# ardTriggerShield.net
KiCad netlist of a schematic drawn in EAGLE
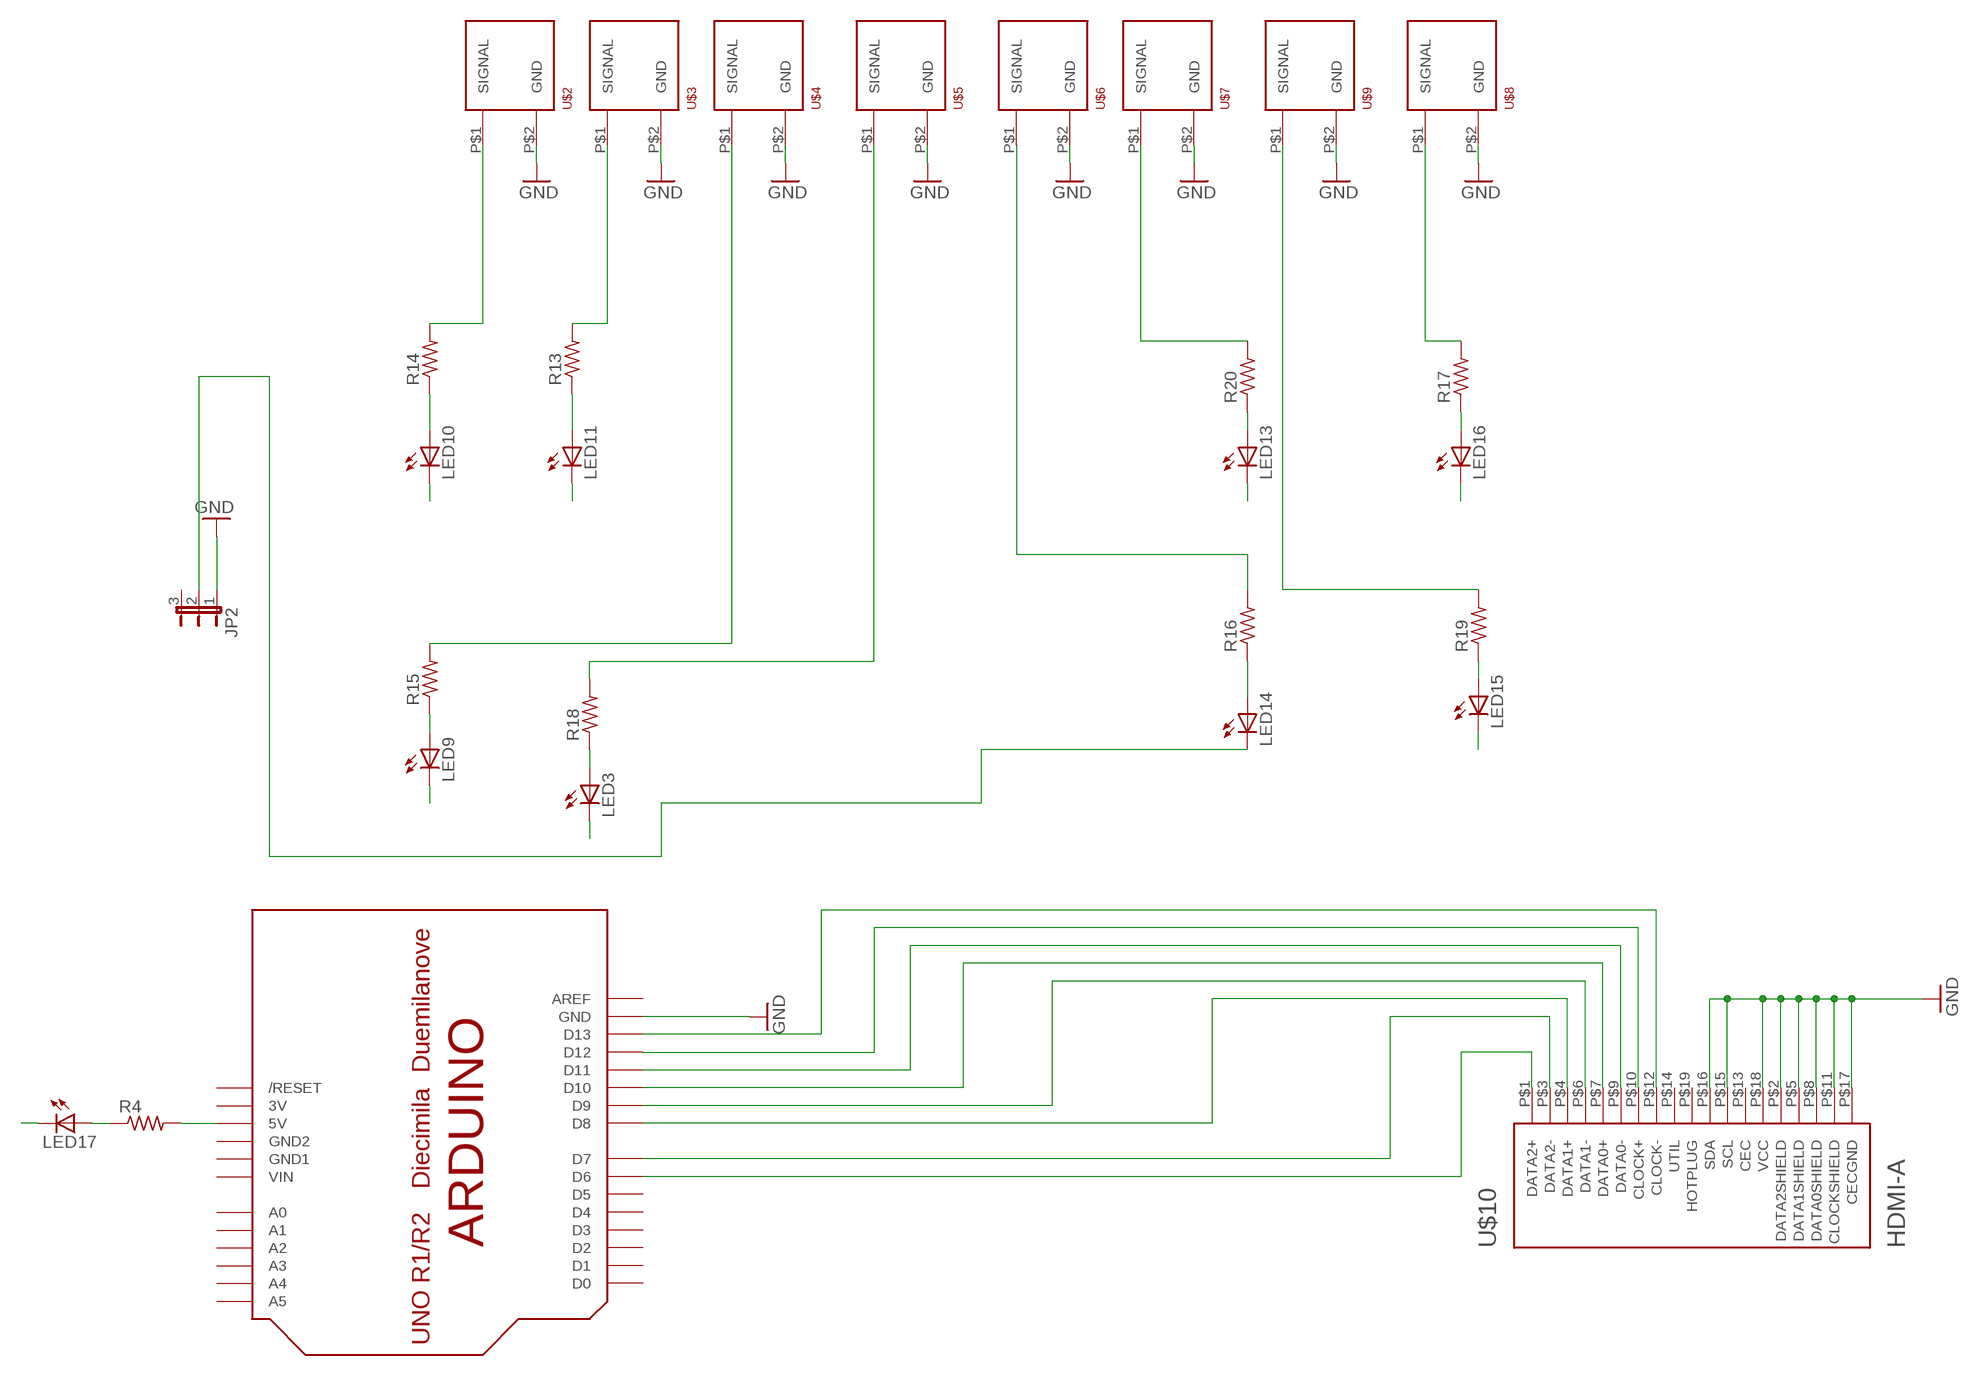
[diagram p0: schematic, sheet 1]

(export (version "E")
  (design (tool "Eeschema 10.0.6"))
  (components
    (comp (ref "JP2")
      (value "JP2E")
      (footprint "eagle-import:JP2")
      (libsource (lib "eagle-import") (part "JP2E"))
    )
    (comp (ref "LED3")
      (value "LEDCHIP-LED0805")
      (footprint "eagle-import:CHIP-LED0805")
      (libsource (lib "eagle-import") (part "LEDCHIP-LED0805"))
    )
    (comp (ref "LED9")
      (value "LEDCHIP-LED0805")
      (footprint "eagle-import:CHIP-LED0805")
      (libsource (lib "eagle-import") (part "LEDCHIP-LED0805"))
    )
    (comp (ref "LED10")
      (value "LEDCHIP-LED0805")
      (footprint "eagle-import:CHIP-LED0805")
      (libsource (lib "eagle-import") (part "LEDCHIP-LED0805"))
    )
    (comp (ref "LED11")
      (value "LEDCHIP-LED0805")
      (footprint "eagle-import:CHIP-LED0805")
      (libsource (lib "eagle-import") (part "LEDCHIP-LED0805"))
    )
    (comp (ref "LED13")
      (value "LEDCHIP-LED0805")
      (footprint "eagle-import:CHIP-LED0805")
      (libsource (lib "eagle-import") (part "LEDCHIP-LED0805"))
    )
    (comp (ref "LED14")
      (value "LEDCHIP-LED0805")
      (footprint "eagle-import:CHIP-LED0805")
      (libsource (lib "eagle-import") (part "LEDCHIP-LED0805"))
    )
    (comp (ref "LED15")
      (value "LEDCHIP-LED0805")
      (footprint "eagle-import:CHIP-LED0805")
      (libsource (lib "eagle-import") (part "LEDCHIP-LED0805"))
    )
    (comp (ref "LED16")
      (value "LEDCHIP-LED0805")
      (footprint "eagle-import:CHIP-LED0805")
      (libsource (lib "eagle-import") (part "LEDCHIP-LED0805"))
    )
    (comp (ref "LED17")
      (value "LEDCHIP-LED0805")
      (footprint "eagle-import:CHIP-LED0805")
      (libsource (lib "eagle-import") (part "LEDCHIP-LED0805"))
    )
    (comp (ref "R4")
      (value "R_0603")
      (footprint "eagle-import:0603")
      (libsource (lib "eagle-import") (part "R_0603"))
    )
    (comp (ref "R13")
      (value "R_0603")
      (footprint "eagle-import:0603")
      (libsource (lib "eagle-import") (part "R_0603"))
    )
    (comp (ref "R14")
      (value "R_0603")
      (footprint "eagle-import:0603")
      (libsource (lib "eagle-import") (part "R_0603"))
    )
    (comp (ref "R15")
      (value "R_0603")
      (footprint "eagle-import:0603")
      (libsource (lib "eagle-import") (part "R_0603"))
    )
    (comp (ref "R16")
      (value "R_0603")
      (footprint "eagle-import:0603")
      (libsource (lib "eagle-import") (part "R_0603"))
    )
    (comp (ref "R17")
      (value "R_0603")
      (footprint "eagle-import:0603")
      (libsource (lib "eagle-import") (part "R_0603"))
    )
    (comp (ref "R18")
      (value "R_0603")
      (footprint "eagle-import:0603")
      (libsource (lib "eagle-import") (part "R_0603"))
    )
    (comp (ref "R19")
      (value "R_0603")
      (footprint "eagle-import:0603")
      (libsource (lib "eagle-import") (part "R_0603"))
    )
    (comp (ref "R20")
      (value "R_0603")
      (footprint "eagle-import:0603")
      (libsource (lib "eagle-import") (part "R_0603"))
    )
    (comp (ref "U$1")
      (value "ARDUINO-NOHOLE")
      (footprint "eagle-import:ARDUINO-NOHOLE")
      (libsource (lib "eagle-import") (part "ARDUINO-NOHOLE"))
    )
    (comp (ref "U$2")
      (value "BNC_VERTICAL")
      (footprint "eagle-import:BNC_VERTICAL")
      (libsource (lib "eagle-import") (part "BNC_VERTICAL"))
    )
    (comp (ref "U$3")
      (value "BNC_VERTICAL")
      (footprint "eagle-import:BNC_VERTICAL")
      (libsource (lib "eagle-import") (part "BNC_VERTICAL"))
    )
    (comp (ref "U$4")
      (value "BNC_VERTICAL")
      (footprint "eagle-import:BNC_VERTICAL")
      (libsource (lib "eagle-import") (part "BNC_VERTICAL"))
    )
    (comp (ref "U$5")
      (value "BNC_VERTICAL")
      (footprint "eagle-import:BNC_VERTICAL")
      (libsource (lib "eagle-import") (part "BNC_VERTICAL"))
    )
    (comp (ref "U$6")
      (value "BNC_VERTICAL")
      (footprint "eagle-import:BNC_VERTICAL")
      (libsource (lib "eagle-import") (part "BNC_VERTICAL"))
    )
    (comp (ref "U$7")
      (value "BNC_VERTICAL")
      (footprint "eagle-import:BNC_VERTICAL")
      (libsource (lib "eagle-import") (part "BNC_VERTICAL"))
    )
    (comp (ref "U$8")
      (value "BNC_VERTICAL")
      (footprint "eagle-import:BNC_VERTICAL")
      (libsource (lib "eagle-import") (part "BNC_VERTICAL"))
    )
    (comp (ref "U$9")
      (value "BNC_VERTICAL")
      (footprint "eagle-import:BNC_VERTICAL")
      (libsource (lib "eagle-import") (part "BNC_VERTICAL"))
    )
    (comp (ref "U$10")
      (value "HDMI-A")
      (footprint "eagle-import:HDMI_A")
      (libsource (lib "eagle-import") (part "HDMI-A"))
    )
  )
  (nets
    (net (code "1") (name "/3V") (class "Default")
      (node (ref "U$1") (pin "3V") (pinfunction "3V_3V") (pintype "power_in"))
    )
    (net (code "2") (name "/D6") (class "Default")
      (node (ref "R17") (pin "2") (pinfunction "2_2") (pintype "passive"))
      (node (ref "U$1") (pin "D6") (pinfunction "D6_D6") (pintype "bidirectional"))
      (node (ref "U$10") (pin "P$1") (pinfunction "DATA2+_P$1") (pintype "bidirectional"))
      (node (ref "U$8") (pin "P$1") (pinfunction "SIGNAL_P$1") (pintype "bidirectional"))
    )
    (net (code "3") (name "/D7") (class "Default")
      (node (ref "R19") (pin "2") (pinfunction "2_2") (pintype "passive"))
      (node (ref "U$1") (pin "D7") (pinfunction "D7_D7") (pintype "bidirectional"))
      (node (ref "U$10") (pin "P$3") (pinfunction "DATA2-_P$3") (pintype "bidirectional"))
      (node (ref "U$9") (pin "P$1") (pinfunction "SIGNAL_P$1") (pintype "bidirectional"))
    )
    (net (code "4") (name "/D8") (class "Default")
      (node (ref "R20") (pin "2") (pinfunction "2_2") (pintype "passive"))
      (node (ref "U$1") (pin "D8") (pinfunction "D8_D8") (pintype "bidirectional"))
      (node (ref "U$10") (pin "P$4") (pinfunction "DATA1+_P$4") (pintype "bidirectional"))
      (node (ref "U$7") (pin "P$1") (pinfunction "SIGNAL_P$1") (pintype "bidirectional"))
    )
    (net (code "5") (name "/D9") (class "Default")
      (node (ref "R16") (pin "2") (pinfunction "2_2") (pintype "passive"))
      (node (ref "U$1") (pin "D9") (pinfunction "D9_D9") (pintype "bidirectional"))
      (node (ref "U$10") (pin "P$6") (pinfunction "DATA1-_P$6") (pintype "bidirectional"))
      (node (ref "U$6") (pin "P$1") (pinfunction "SIGNAL_P$1") (pintype "bidirectional"))
    )
    (net (code "6") (name "/D10") (class "Default")
      (node (ref "R18") (pin "2") (pinfunction "2_2") (pintype "passive"))
      (node (ref "U$1") (pin "D10") (pinfunction "D10_D10") (pintype "bidirectional"))
      (node (ref "U$10") (pin "P$7") (pinfunction "DATA0+_P$7") (pintype "bidirectional"))
      (node (ref "U$5") (pin "P$1") (pinfunction "SIGNAL_P$1") (pintype "bidirectional"))
    )
    (net (code "7") (name "/D11") (class "Default")
      (node (ref "R15") (pin "2") (pinfunction "2_2") (pintype "passive"))
      (node (ref "U$1") (pin "D11") (pinfunction "D11_D11") (pintype "bidirectional"))
      (node (ref "U$10") (pin "P$9") (pinfunction "DATA0-_P$9") (pintype "bidirectional"))
      (node (ref "U$4") (pin "P$1") (pinfunction "SIGNAL_P$1") (pintype "bidirectional"))
    )
    (net (code "8") (name "/D12") (class "Default")
      (node (ref "R13") (pin "2") (pinfunction "2_2") (pintype "passive"))
      (node (ref "U$1") (pin "D12") (pinfunction "D12_D12") (pintype "bidirectional"))
      (node (ref "U$10") (pin "P$10") (pinfunction "CLOCK+_P$10") (pintype "bidirectional"))
      (node (ref "U$3") (pin "P$1") (pinfunction "SIGNAL_P$1") (pintype "bidirectional"))
    )
    (net (code "9") (name "/D13") (class "Default")
      (node (ref "R14") (pin "2") (pinfunction "2_2") (pintype "passive"))
      (node (ref "U$1") (pin "D13") (pinfunction "D13_D13") (pintype "bidirectional"))
      (node (ref "U$10") (pin "P$12") (pinfunction "CLOCK-_P$12") (pintype "bidirectional"))
      (node (ref "U$2") (pin "P$1") (pinfunction "SIGNAL_P$1") (pintype "bidirectional"))
    )
    (net (code "10") (name "/GND1") (class "Default")
      (node (ref "U$1") (pin "GND1") (pinfunction "GND1_GND1") (pintype "power_in"))
    )
    (net (code "11") (name "/GND2") (class "Default")
      (node (ref "U$1") (pin "GND2") (pinfunction "GND2_GND2") (pintype "power_in"))
    )
    (net (code "12") (name "/LED") (class "Default")
      (node (ref "JP2") (pin "2") (pinfunction "2_2") (pintype "passive"))
      (node (ref "LED10") (pin "C") (pinfunction "C_C") (pintype "passive"))
      (node (ref "LED11") (pin "C") (pinfunction "C_C") (pintype "passive"))
      (node (ref "LED13") (pin "C") (pinfunction "C_C") (pintype "passive"))
      (node (ref "LED14") (pin "C") (pinfunction "C_C") (pintype "passive"))
      (node (ref "LED15") (pin "C") (pinfunction "C_C") (pintype "passive"))
      (node (ref "LED16") (pin "C") (pinfunction "C_C") (pintype "passive"))
      (node (ref "LED17") (pin "C") (pinfunction "C_C") (pintype "passive"))
      (node (ref "LED3") (pin "C") (pinfunction "C_C") (pintype "passive"))
      (node (ref "LED9") (pin "C") (pinfunction "C_C") (pintype "passive"))
    )
    (net (code "13") (name "/VIN") (class "Default")
      (node (ref "U$1") (pin "VIN") (pinfunction "VIN_VIN") (pintype "power_in"))
    )
    (net (code "14") (name "GND") (class "Default")
      (node (ref "JP2") (pin "1") (pinfunction "1_1") (pintype "passive"))
      (node (ref "U$1") (pin "GND") (pinfunction "GND_GND") (pintype "power_in"))
      (node (ref "U$10") (pin "P$11") (pinfunction "CLOCKSHIELD_P$11") (pintype "bidirectional"))
      (node (ref "U$10") (pin "P$15") (pinfunction "SCL_P$15") (pintype "bidirectional"))
      (node (ref "U$10") (pin "P$16") (pinfunction "SDA_P$16") (pintype "bidirectional"))
      (node (ref "U$10") (pin "P$17") (pinfunction "CECGND_P$17") (pintype "bidirectional"))
      (node (ref "U$10") (pin "P$18") (pinfunction "VCC_P$18") (pintype "bidirectional"))
      (node (ref "U$10") (pin "P$2") (pinfunction "DATA2SHIELD_P$2") (pintype "bidirectional"))
      (node (ref "U$10") (pin "P$5") (pinfunction "DATA1SHIELD_P$5") (pintype "bidirectional"))
      (node (ref "U$10") (pin "P$8") (pinfunction "DATA0SHIELD_P$8") (pintype "bidirectional"))
      (node (ref "U$2") (pin "P$2") (pinfunction "GND_P$2") (pintype "bidirectional"))
      (node (ref "U$3") (pin "P$2") (pinfunction "GND_P$2") (pintype "bidirectional"))
      (node (ref "U$4") (pin "P$2") (pinfunction "GND_P$2") (pintype "bidirectional"))
      (node (ref "U$5") (pin "P$2") (pinfunction "GND_P$2") (pintype "bidirectional"))
      (node (ref "U$6") (pin "P$2") (pinfunction "GND_P$2") (pintype "bidirectional"))
      (node (ref "U$7") (pin "P$2") (pinfunction "GND_P$2") (pintype "bidirectional"))
      (node (ref "U$8") (pin "P$2") (pinfunction "GND_P$2") (pintype "bidirectional"))
      (node (ref "U$9") (pin "P$2") (pinfunction "GND_P$2") (pintype "bidirectional"))
    )
    (net (code "15") (name "Net-(LED3-PadA)") (class "Default")
      (node (ref "LED3") (pin "A") (pinfunction "A_A") (pintype "passive"))
      (node (ref "R18") (pin "1") (pinfunction "1_1") (pintype "passive"))
    )
    (net (code "16") (name "Net-(LED9-PadA)") (class "Default")
      (node (ref "LED9") (pin "A") (pinfunction "A_A") (pintype "passive"))
      (node (ref "R15") (pin "1") (pinfunction "1_1") (pintype "passive"))
    )
    (net (code "17") (name "Net-(LED10-PadA)") (class "Default")
      (node (ref "LED10") (pin "A") (pinfunction "A_A") (pintype "passive"))
      (node (ref "R14") (pin "1") (pinfunction "1_1") (pintype "passive"))
    )
    (net (code "18") (name "Net-(LED11-PadA)") (class "Default")
      (node (ref "LED11") (pin "A") (pinfunction "A_A") (pintype "passive"))
      (node (ref "R13") (pin "1") (pinfunction "1_1") (pintype "passive"))
    )
    (net (code "19") (name "Net-(LED13-PadA)") (class "Default")
      (node (ref "LED13") (pin "A") (pinfunction "A_A") (pintype "passive"))
      (node (ref "R20") (pin "1") (pinfunction "1_1") (pintype "passive"))
    )
    (net (code "20") (name "Net-(LED14-PadA)") (class "Default")
      (node (ref "LED14") (pin "A") (pinfunction "A_A") (pintype "passive"))
      (node (ref "R16") (pin "1") (pinfunction "1_1") (pintype "passive"))
    )
    (net (code "21") (name "Net-(LED15-PadA)") (class "Default")
      (node (ref "LED15") (pin "A") (pinfunction "A_A") (pintype "passive"))
      (node (ref "R19") (pin "1") (pinfunction "1_1") (pintype "passive"))
    )
    (net (code "22") (name "Net-(LED16-PadA)") (class "Default")
      (node (ref "LED16") (pin "A") (pinfunction "A_A") (pintype "passive"))
      (node (ref "R17") (pin "1") (pinfunction "1_1") (pintype "passive"))
    )
    (net (code "23") (name "Net-(LED17-PadA)") (class "Default")
      (node (ref "LED17") (pin "A") (pinfunction "A_A") (pintype "passive"))
      (node (ref "R4") (pin "1") (pinfunction "1_1") (pintype "passive"))
    )
    (net (code "24") (name "Net-(R4-Pad2)") (class "Default")
      (node (ref "R4") (pin "2") (pinfunction "2_2") (pintype "passive"))
      (node (ref "U$1") (pin "5V") (pinfunction "5V_5V") (pintype "power_in"))
    )
    (net (code "25") (name "unconnected-(JP2-Pad3)") (class "Default")
      (node (ref "JP2") (pin "3") (pinfunction "3_3") (pintype "passive"))
    )
    (net (code "26") (name "unconnected-(U$1-PadA0)") (class "Default")
      (node (ref "U$1") (pin "A0") (pinfunction "A0_A0") (pintype "bidirectional"))
    )
    (net (code "27") (name "unconnected-(U$1-PadA1)") (class "Default")
      (node (ref "U$1") (pin "A1") (pinfunction "A1_A1") (pintype "bidirectional"))
    )
    (net (code "28") (name "unconnected-(U$1-PadA2)") (class "Default")
      (node (ref "U$1") (pin "A2") (pinfunction "A2_A2") (pintype "bidirectional"))
    )
    (net (code "29") (name "unconnected-(U$1-PadA3)") (class "Default")
      (node (ref "U$1") (pin "A3") (pinfunction "A3_A3") (pintype "bidirectional"))
    )
    (net (code "30") (name "unconnected-(U$1-PadA4)") (class "Default")
      (node (ref "U$1") (pin "A4") (pinfunction "A4_A4") (pintype "bidirectional"))
    )
    (net (code "31") (name "unconnected-(U$1-PadA5)") (class "Default")
      (node (ref "U$1") (pin "A5") (pinfunction "A5_A5") (pintype "bidirectional"))
    )
    (net (code "32") (name "unconnected-(U$1-PadAREF)") (class "Default")
      (node (ref "U$1") (pin "AREF") (pinfunction "AREF_AREF") (pintype "bidirectional"))
    )
    (net (code "33") (name "unconnected-(U$1-PadD0)") (class "Default")
      (node (ref "U$1") (pin "D0") (pinfunction "D0_D0") (pintype "bidirectional"))
    )
    (net (code "34") (name "unconnected-(U$1-PadD1)") (class "Default")
      (node (ref "U$1") (pin "D1") (pinfunction "D1_D1") (pintype "bidirectional"))
    )
    (net (code "35") (name "unconnected-(U$1-PadD2)") (class "Default")
      (node (ref "U$1") (pin "D2") (pinfunction "D2_D2") (pintype "bidirectional"))
    )
    (net (code "36") (name "unconnected-(U$1-PadD3)") (class "Default")
      (node (ref "U$1") (pin "D3") (pinfunction "D3_D3") (pintype "bidirectional"))
    )
    (net (code "37") (name "unconnected-(U$1-PadD4)") (class "Default")
      (node (ref "U$1") (pin "D4") (pinfunction "D4_D4") (pintype "bidirectional"))
    )
    (net (code "38") (name "unconnected-(U$1-PadD5)") (class "Default")
      (node (ref "U$1") (pin "D5") (pinfunction "D5_D5") (pintype "bidirectional"))
    )
    (net (code "39") (name "unconnected-(U$1-{slash}RESET-PadRESET)") (class "Default")
      (node (ref "U$1") (pin "RESET") (pinfunction "/RESET_RESET") (pintype "bidirectional"))
    )
    (net (code "40") (name "unconnected-(U$10-CEC-PadP$13)") (class "Default")
      (node (ref "U$10") (pin "P$13") (pinfunction "CEC_P$13") (pintype "bidirectional"))
    )
    (net (code "41") (name "unconnected-(U$10-HOTPLUG-PadP$19)") (class "Default")
      (node (ref "U$10") (pin "P$19") (pinfunction "HOTPLUG_P$19") (pintype "bidirectional"))
    )
    (net (code "42") (name "unconnected-(U$10-UTIL-PadP$14)") (class "Default")
      (node (ref "U$10") (pin "P$14") (pinfunction "UTIL_P$14") (pintype "bidirectional"))
    )
  )
)
